# lat_encamp_v2_axial.net
KiCad netlist of a schematic drawn in EAGLE
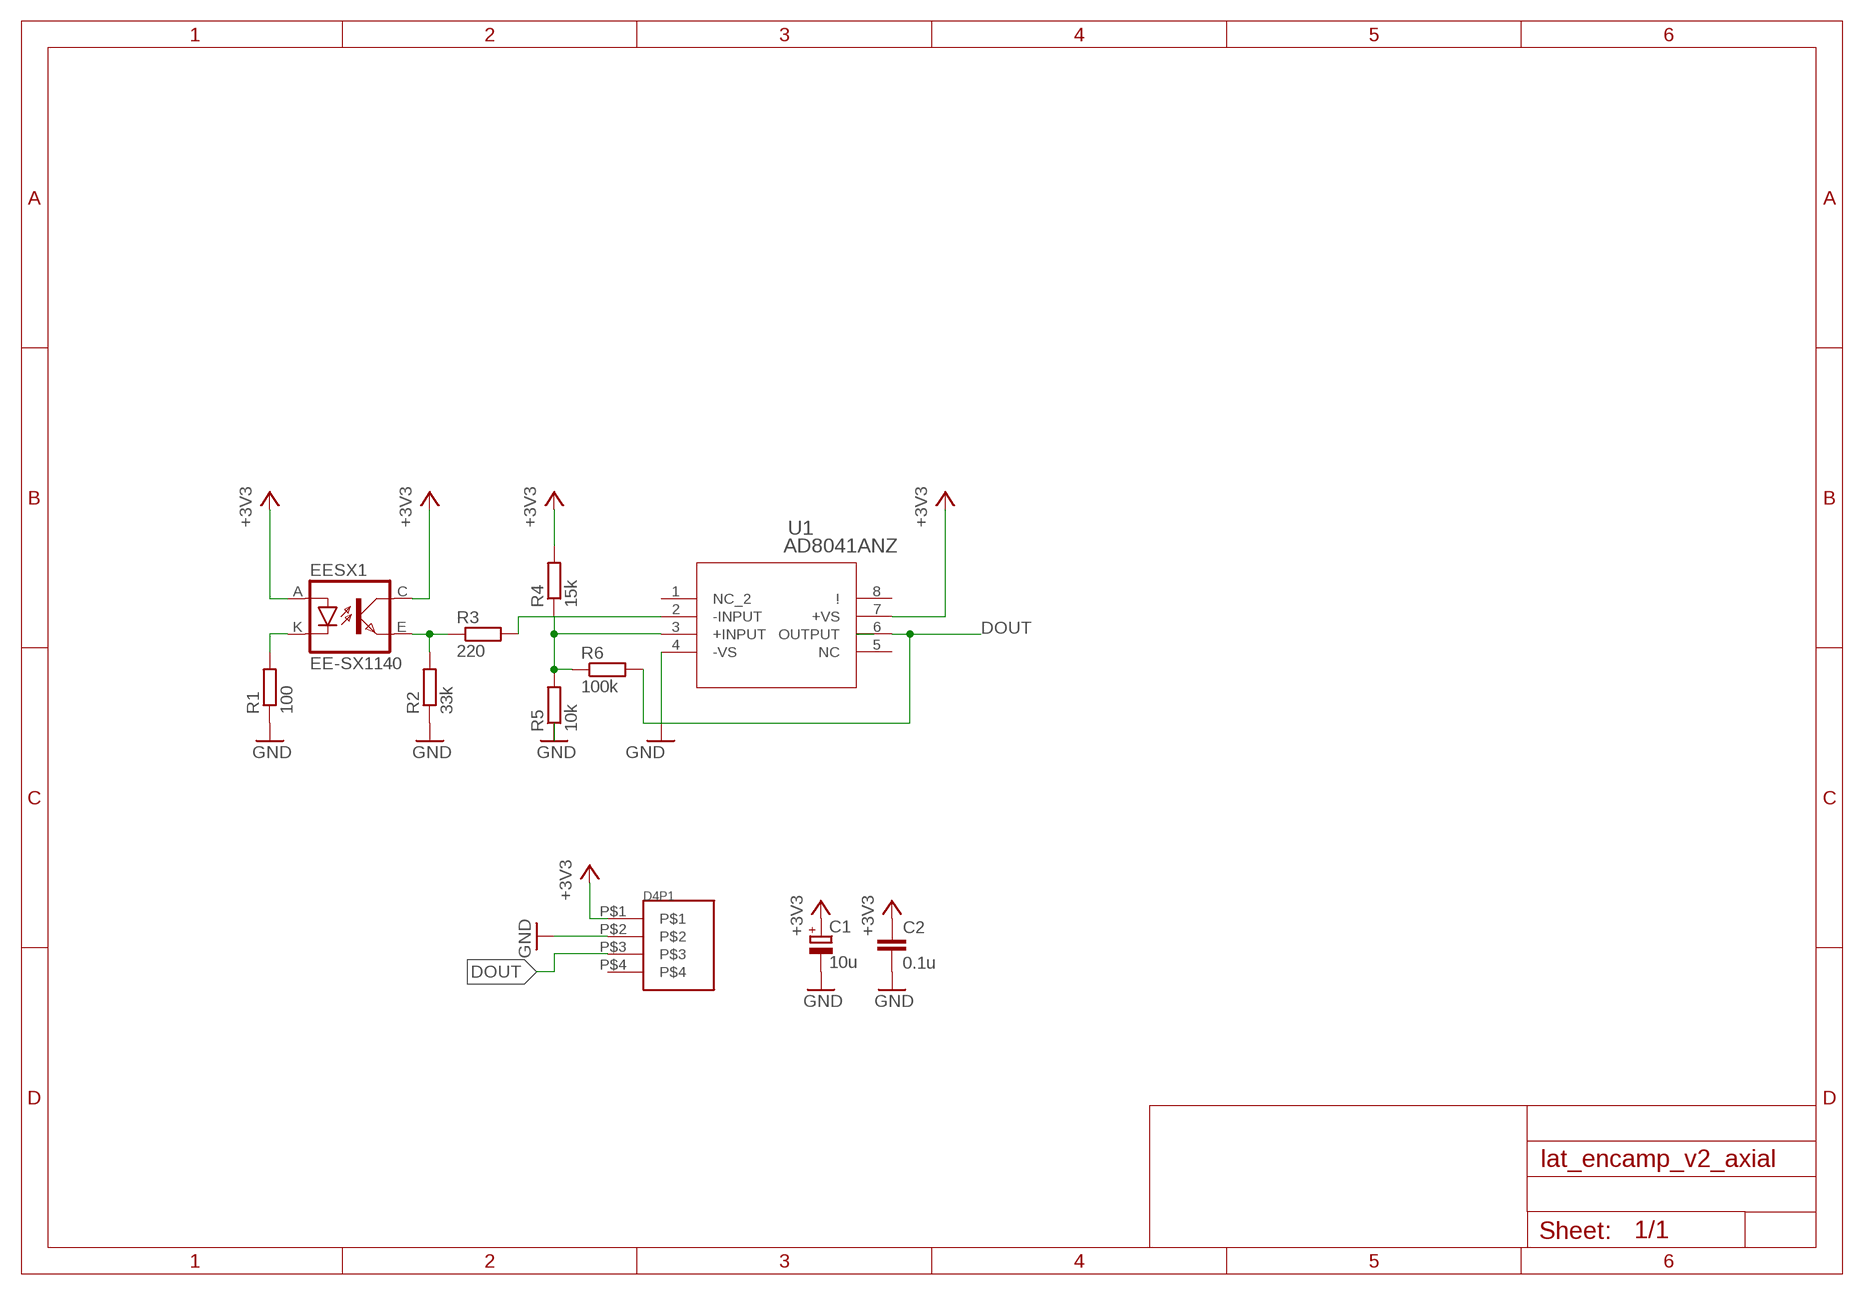
[diagram p0: schematic, sheet 1]

(export (version "E")
  (design (tool "Eeschema 10.0.6"))
  (components
    (comp (ref "C1")
      (value "10u")
      (footprint "eagle-import:E2,5-6E")
      (libsource (lib "eagle-import") (part "CPOL-EUE2,5-6E"))
    )
    (comp (ref "C2")
      (value "0.1u")
      (footprint "eagle-import:C050-024X044")
      (libsource (lib "eagle-import") (part "C-EU050-024X044"))
    )
    (comp (ref "D4P1")
      (value "DF1E-4P")
      (footprint "eagle-import:DF1E-4P")
      (libsource (lib "eagle-import") (part "DF1E-4P"))
    )
    (comp (ref "EESX1")
      (value "EE-SX1140")
      (footprint "eagle-import:EE-SX1140")
      (libsource (lib "eagle-import") (part "EE-SX1140"))
    )
    (comp (ref "R1")
      (value "100")
      (footprint "eagle-import:0204_7")
      (libsource (lib "eagle-import") (part "R-EU_0204/7"))
    )
    (comp (ref "R2")
      (value "33k")
      (footprint "eagle-import:0204_7")
      (libsource (lib "eagle-import") (part "R-EU_0204/7"))
    )
    (comp (ref "R3")
      (value "220")
      (footprint "eagle-import:0204_7")
      (libsource (lib "eagle-import") (part "R-EU_0204/7"))
    )
    (comp (ref "R4")
      (value "15k")
      (footprint "eagle-import:0204_7")
      (libsource (lib "eagle-import") (part "R-EU_0204/7"))
    )
    (comp (ref "R5")
      (value "10k")
      (footprint "eagle-import:0204_7")
      (libsource (lib "eagle-import") (part "R-EU_0204/7"))
    )
    (comp (ref "R6")
      (value "100k")
      (footprint "eagle-import:0204_7")
      (libsource (lib "eagle-import") (part "R-EU_0204/7"))
    )
    (comp (ref "U1")
      (value "AD8041ANZ")
      (footprint "eagle-import:N_8_ADI")
      (libsource (lib "eagle-import") (part "AD8041ANZ"))
    )
  )
  (nets
    (net (code "1") (name "+3V3") (class "Default")
      (node (ref "C1") (pin "+") (pinfunction "+_+") (pintype "passive"))
      (node (ref "C2") (pin "1") (pinfunction "1_1") (pintype "passive"))
      (node (ref "D4P1") (pin "P$1") (pinfunction "P$1_P$1") (pintype "bidirectional"))
      (node (ref "EESX1") (pin "A") (pinfunction "A_A") (pintype "passive"))
      (node (ref "EESX1") (pin "C") (pinfunction "COL_C") (pintype "passive"))
      (node (ref "R4") (pin "2") (pinfunction "2_2") (pintype "passive"))
      (node (ref "U1") (pin "7") (pinfunction "+VS_7") (pintype "power_in"))
    )
    (net (code "2") (name "DOUT") (class "Default")
      (node (ref "D4P1") (pin "P$3") (pinfunction "P$3_P$3") (pintype "bidirectional"))
      (node (ref "R6") (pin "2") (pinfunction "2_2") (pintype "passive"))
      (node (ref "U1") (pin "6") (pinfunction "OUTPUT_6") (pintype "passive"))
    )
    (net (code "3") (name "GND") (class "Default")
      (node (ref "C1") (pin "-") (pinfunction "-_-") (pintype "passive"))
      (node (ref "C2") (pin "2") (pinfunction "2_2") (pintype "passive"))
      (node (ref "D4P1") (pin "P$2") (pinfunction "P$2_P$2") (pintype "bidirectional"))
      (node (ref "R1") (pin "1") (pinfunction "1_1") (pintype "passive"))
      (node (ref "R2") (pin "1") (pinfunction "1_1") (pintype "passive"))
      (node (ref "R5") (pin "1") (pinfunction "1_1") (pintype "passive"))
      (node (ref "U1") (pin "4") (pinfunction "-VS_4") (pintype "power_in"))
    )
    (net (code "4") (name "Net-(EESX1-C)") (class "Default")
      (node (ref "EESX1") (pin "K") (pinfunction "C_K") (pintype "passive"))
      (node (ref "R1") (pin "2") (pinfunction "2_2") (pintype "passive"))
    )
    (net (code "5") (name "Net-(EESX1-EMIT)") (class "Default")
      (node (ref "EESX1") (pin "E") (pinfunction "EMIT_E") (pintype "passive"))
      (node (ref "R2") (pin "2") (pinfunction "2_2") (pintype "passive"))
      (node (ref "R3") (pin "1") (pinfunction "1_1") (pintype "passive"))
    )
    (net (code "6") (name "Net-(U1-+INPUT)") (class "Default")
      (node (ref "R4") (pin "1") (pinfunction "1_1") (pintype "passive"))
      (node (ref "R5") (pin "2") (pinfunction "2_2") (pintype "passive"))
      (node (ref "R6") (pin "1") (pinfunction "1_1") (pintype "passive"))
      (node (ref "U1") (pin "3") (pinfunction "+INPUT_3") (pintype "passive"))
    )
    (net (code "7") (name "Net-(U1--INPUT)") (class "Default")
      (node (ref "R3") (pin "2") (pinfunction "2_2") (pintype "passive"))
      (node (ref "U1") (pin "2") (pinfunction "-INPUT_2") (pintype "passive"))
    )
    (net (code "8") (name "unconnected-(D4P1-PadP$4)") (class "Default")
      (node (ref "D4P1") (pin "P$4") (pinfunction "P$4_P$4") (pintype "bidirectional"))
    )
    (net (code "9") (name "unconnected-(U1-NC-Pad5)") (class "Default")
      (node (ref "U1") (pin "5") (pinfunction "NC_5") (pintype "passive"))
    )
    (net (code "10") (name "unconnected-(U1-NC_2-Pad1)") (class "Default")
      (node (ref "U1") (pin "1") (pinfunction "NC_2_1") (pintype "passive"))
    )
    (net (code "11") (name "unconnected-(U1-~-Pad8)") (class "Default")
      (node (ref "U1") (pin "8") (pinfunction "~_8") (pintype "passive"))
    )
  )
)
